# Ada.net
KiCad netlist of a schematic drawn in EAGLE
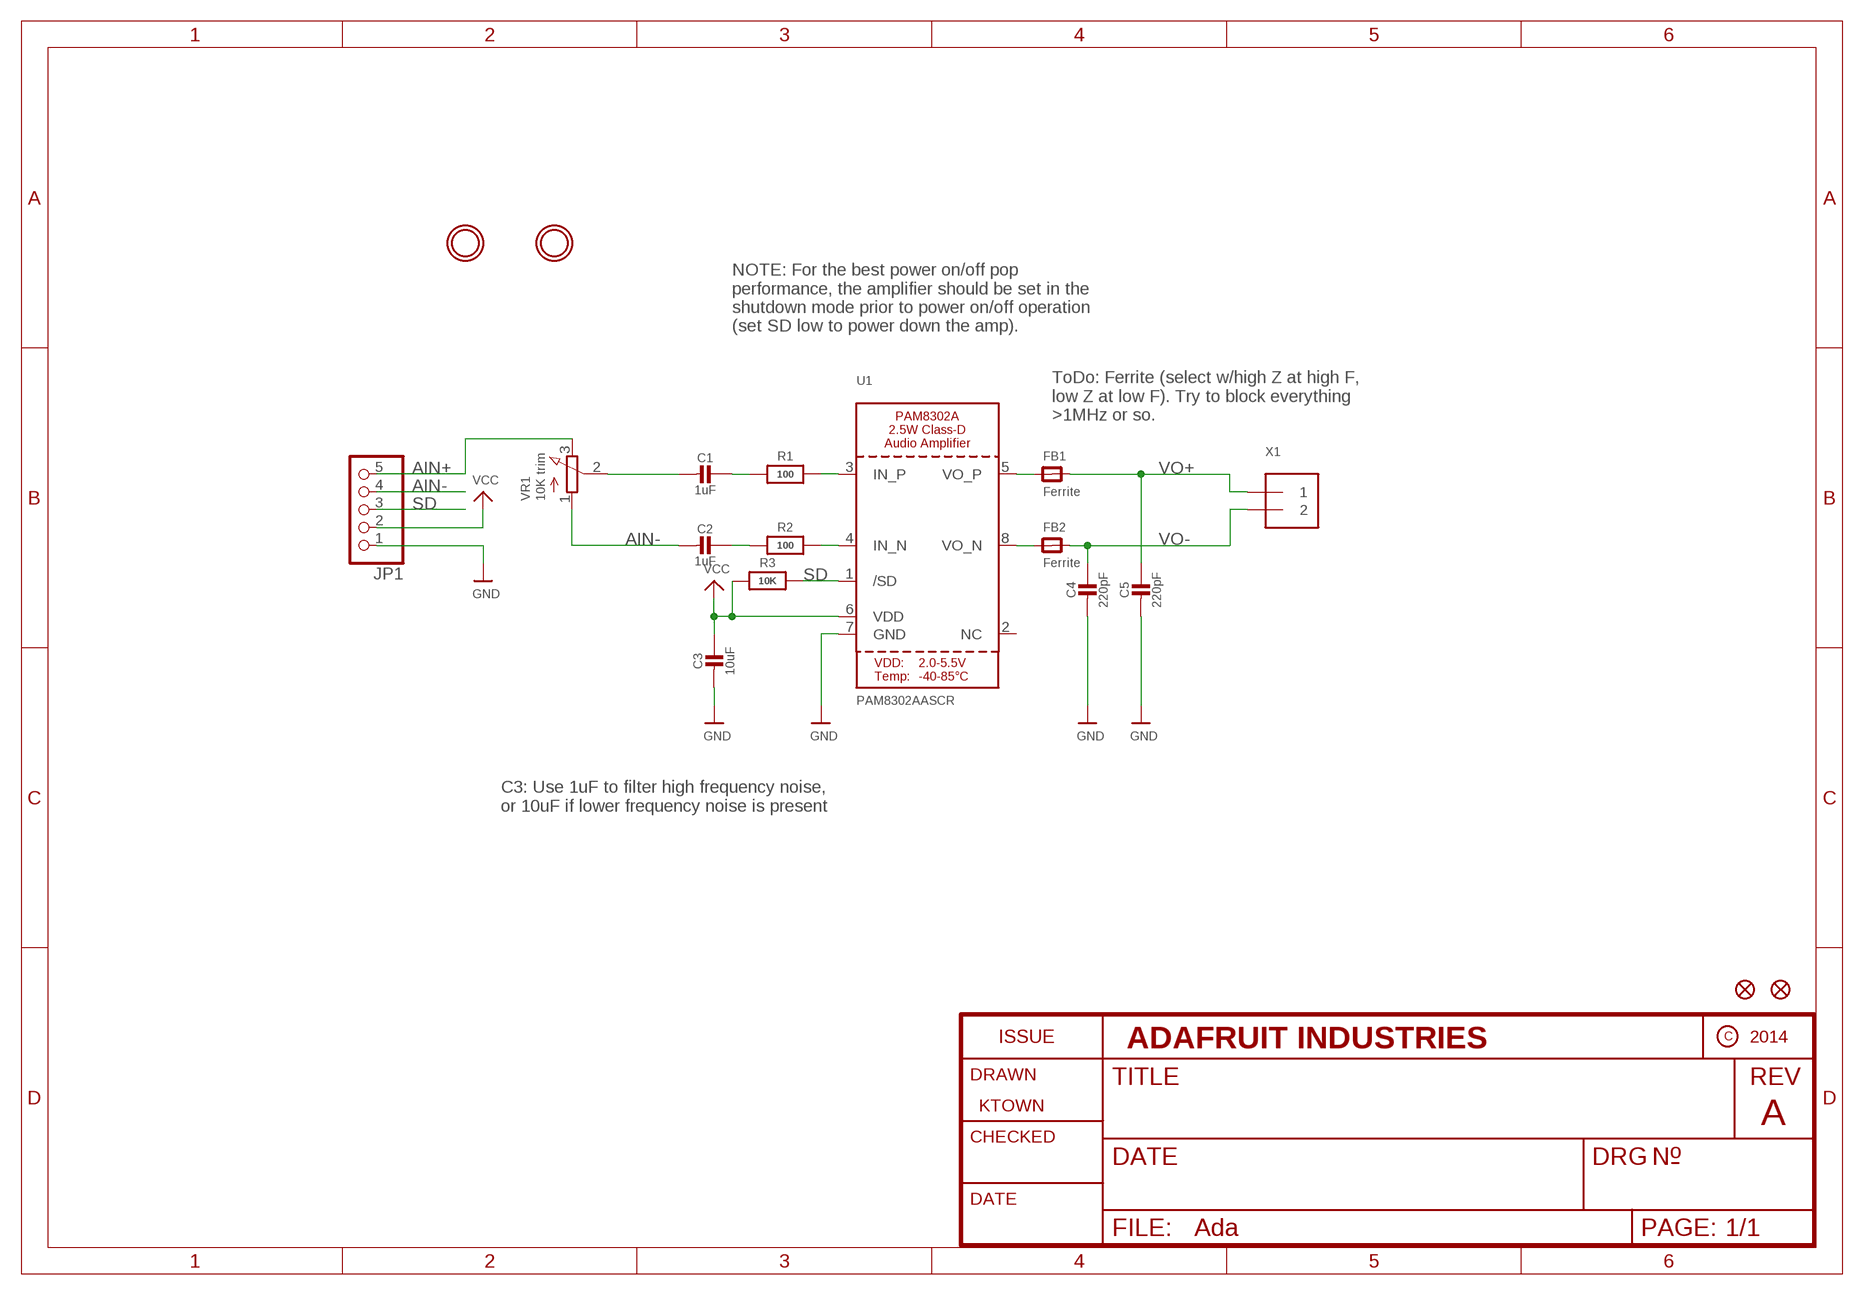
[diagram p0: schematic, sheet 1]

(export (version "E")
  (design (tool "Eeschema 10.0.6"))
  (components
    (comp (ref "C1")
      (value "1uF")
      (footprint "eagle-import:0805-NO")
      (libsource (lib "eagle-import") (part "CAP_CERAMIC0805-NOOUTLINE"))
    )
    (comp (ref "C2")
      (value "1uF")
      (footprint "eagle-import:0805-NO")
      (libsource (lib "eagle-import") (part "CAP_CERAMIC0805-NOOUTLINE"))
    )
    (comp (ref "C3")
      (value "10uF")
      (footprint "eagle-import:0805-NO")
      (libsource (lib "eagle-import") (part "CAP_CERAMIC0805-NOOUTLINE"))
    )
    (comp (ref "C4")
      (value "220pF")
      (footprint "eagle-import:0805-NO")
      (libsource (lib "eagle-import") (part "CAP_CERAMIC0805-NOOUTLINE"))
    )
    (comp (ref "C5")
      (value "220pF")
      (footprint "eagle-import:0805-NO")
      (libsource (lib "eagle-import") (part "CAP_CERAMIC0805-NOOUTLINE"))
    )
    (comp (ref "FB1")
      (value "Ferrite")
      (footprint "eagle-import:_0805")
      (libsource (lib "eagle-import") (part "FERRITE_0805"))
    )
    (comp (ref "FB2")
      (value "Ferrite")
      (footprint "eagle-import:_0805")
      (libsource (lib "eagle-import") (part "FERRITE_0805"))
    )
    (comp (ref "FID1")
      (value "FIDUCIAL\"\"")
      (footprint "eagle-import:FIDUCIAL_1MM")
      (libsource (lib "eagle-import") (part "FIDUCIAL{dblquote}{dblquote}"))
    )
    (comp (ref "FID2")
      (value "FIDUCIAL\"\"")
      (footprint "eagle-import:FIDUCIAL_1MM")
      (libsource (lib "eagle-import") (part "FIDUCIAL{dblquote}{dblquote}"))
    )
    (comp (ref "JP1")
      (value "HEADER-1X570MIL")
      (footprint "eagle-import:1X05_ROUND_70")
      (libsource (lib "eagle-import") (part "HEADER-1X570MIL"))
    )
    (comp (ref "R1")
      (value "100")
      (footprint "eagle-import:0805-NO")
      (libsource (lib "eagle-import") (part "RESISTOR0805_NOOUTLINE"))
    )
    (comp (ref "R2")
      (value "100")
      (footprint "eagle-import:0805-NO")
      (libsource (lib "eagle-import") (part "RESISTOR0805_NOOUTLINE"))
    )
    (comp (ref "R3")
      (value "10K")
      (footprint "eagle-import:0805-NO")
      (libsource (lib "eagle-import") (part "RESISTOR0805_NOOUTLINE"))
    )
    (comp (ref "U$10")
      (value "MOUNTINGHOLE2.0")
      (footprint "eagle-import:MOUNTINGHOLE_2.0_PLATED")
      (libsource (lib "eagle-import") (part "MOUNTINGHOLE2.0"))
    )
    (comp (ref "U$11")
      (value "MOUNTINGHOLE2.0")
      (footprint "eagle-import:MOUNTINGHOLE_2.0_PLATED")
      (libsource (lib "eagle-import") (part "MOUNTINGHOLE2.0"))
    )
    (comp (ref "U1")
      (value "PAM8302AASCR")
      (footprint "eagle-import:MSOP8_0.65MM")
      (libsource (lib "eagle-import") (part "AUDIOAMP_PAM8302A"))
    )
    (comp (ref "VR1")
      (value "10K trim")
      (footprint "eagle-import:TRIMPOT_BOURNS_3303W")
      (libsource (lib "eagle-import") (part "TRIMPOT3303W/X"))
    )
    (comp (ref "X1")
      (value "TERMBLOCK_1X2")
      (footprint "eagle-import:TERMBLOCK_1X2-3.5MM")
      (libsource (lib "eagle-import") (part "TERMBLOCK_1X2"))
    )
  )
  (nets
    (net (code "1") (name "/AIN+") (class "Default")
      (node (ref "JP1") (pin "5") (pinfunction "5_5") (pintype "passive"))
      (node (ref "VR1") (pin "3") (pinfunction "E_3") (pintype "passive"))
    )
    (net (code "2") (name "/AIN-") (class "Default")
      (node (ref "C2") (pin "2") (pinfunction "2_2") (pintype "passive"))
      (node (ref "JP1") (pin "4") (pinfunction "4_4") (pintype "passive"))
      (node (ref "VR1") (pin "1") (pinfunction "A_1") (pintype "passive"))
    )
    (net (code "3") (name "/SD") (class "Default")
      (node (ref "JP1") (pin "3") (pinfunction "3_3") (pintype "passive"))
      (node (ref "R3") (pin "2") (pinfunction "2_2") (pintype "passive"))
      (node (ref "U1") (pin "1") (pinfunction "/SD_1") (pintype "input"))
    )
    (net (code "4") (name "/VO+") (class "Default")
      (node (ref "C5") (pin "1") (pinfunction "1_1") (pintype "passive"))
      (node (ref "FB1") (pin "2") (pinfunction "P$2_2") (pintype "passive"))
      (node (ref "X1") (pin "1") (pinfunction "1_1") (pintype "passive"))
    )
    (net (code "5") (name "/VO-") (class "Default")
      (node (ref "C4") (pin "1") (pinfunction "1_1") (pintype "passive"))
      (node (ref "FB2") (pin "2") (pinfunction "P$2_2") (pintype "passive"))
      (node (ref "X1") (pin "2") (pinfunction "2_2") (pintype "passive"))
    )
    (net (code "6") (name "GND") (class "Default")
      (node (ref "C3") (pin "2") (pinfunction "2_2") (pintype "passive"))
      (node (ref "C4") (pin "2") (pinfunction "2_2") (pintype "passive"))
      (node (ref "C5") (pin "2") (pinfunction "2_2") (pintype "passive"))
      (node (ref "JP1") (pin "1") (pinfunction "1_1") (pintype "passive"))
      (node (ref "U1") (pin "7") (pinfunction "GND_7") (pintype "power_in"))
    )
    (net (code "7") (name "Net-(C1-Pad1)") (class "Default")
      (node (ref "C1") (pin "1") (pinfunction "1_1") (pintype "passive"))
      (node (ref "R1") (pin "1") (pinfunction "1_1") (pintype "passive"))
    )
    (net (code "8") (name "Net-(C2-Pad1)") (class "Default")
      (node (ref "C2") (pin "1") (pinfunction "1_1") (pintype "passive"))
      (node (ref "R2") (pin "1") (pinfunction "1_1") (pintype "passive"))
    )
    (net (code "9") (name "Net-(FB1-P$1)") (class "Default")
      (node (ref "FB1") (pin "1") (pinfunction "P$1_1") (pintype "passive"))
      (node (ref "U1") (pin "5") (pinfunction "VO_P_5") (pintype "output"))
    )
    (net (code "10") (name "Net-(FB2-P$1)") (class "Default")
      (node (ref "FB2") (pin "1") (pinfunction "P$1_1") (pintype "passive"))
      (node (ref "U1") (pin "8") (pinfunction "VO_N_8") (pintype "output"))
    )
    (net (code "11") (name "Net-(U1-IN_N)") (class "Default")
      (node (ref "R2") (pin "2") (pinfunction "2_2") (pintype "passive"))
      (node (ref "U1") (pin "4") (pinfunction "IN_N_4") (pintype "input"))
    )
    (net (code "12") (name "Net-(U1-IN_P)") (class "Default")
      (node (ref "R1") (pin "2") (pinfunction "2_2") (pintype "passive"))
      (node (ref "U1") (pin "3") (pinfunction "IN_P_3") (pintype "input"))
    )
    (net (code "13") (name "Net-(VR1-S)") (class "Default")
      (node (ref "C1") (pin "2") (pinfunction "2_2") (pintype "passive"))
      (node (ref "VR1") (pin "2") (pinfunction "S_2") (pintype "passive"))
    )
    (net (code "14") (name "VCC") (class "Default")
      (node (ref "C3") (pin "1") (pinfunction "1_1") (pintype "passive"))
      (node (ref "JP1") (pin "2") (pinfunction "2_2") (pintype "passive"))
      (node (ref "R3") (pin "1") (pinfunction "1_1") (pintype "passive"))
      (node (ref "U1") (pin "6") (pinfunction "VDD_6") (pintype "power_in"))
    )
    (net (code "15") (name "unconnected-(U1-NC-Pad2)") (class "Default")
      (node (ref "U1") (pin "2") (pinfunction "NC_2") (pintype "no_connect"))
    )
  )
)
